# ProPrj_MID360V2_0_2025-05-30.net
KiCad netlist of a schematic drawn in EasyEDA Pro
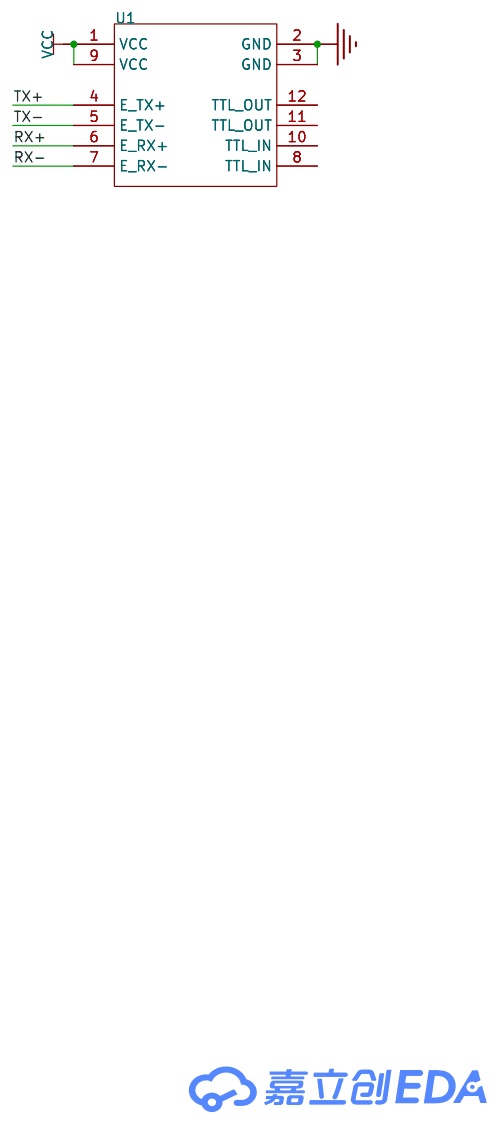
[diagram p0: schematic sheet]

(export (version "E")
  (design (tool "Eeschema 10.0.6"))
  (components
    (comp (ref "U1")
      (value "~")
      (footprint "easyedapro:M12_A_12")
      (libsource (lib "easyedapro") (part "mid360_m12"))
    )
  )
  (nets
    (net (code "1") (name "/RX+") (class "Default")
      (node (ref "U1") (pin "6") (pinfunction "E_RX+_6") (pintype "input"))
    )
    (net (code "2") (name "/RX-") (class "Default")
      (node (ref "U1") (pin "7") (pinfunction "E_RX-_7") (pintype "input"))
    )
    (net (code "3") (name "/TX+") (class "Default")
      (node (ref "U1") (pin "4") (pinfunction "E_TX+_4") (pintype "input"))
    )
    (net (code "4") (name "/TX-") (class "Default")
      (node (ref "U1") (pin "5") (pinfunction "E_TX-_5") (pintype "input"))
    )
    (net (code "5") (name "GND") (class "Default")
      (node (ref "U1") (pin "2") (pinfunction "GND_2") (pintype "input"))
      (node (ref "U1") (pin "3") (pinfunction "GND_3") (pintype "input"))
    )
    (net (code "6") (name "VCC") (class "Default")
      (node (ref "U1") (pin "1") (pinfunction "VCC_1") (pintype "input"))
      (node (ref "U1") (pin "9") (pinfunction "VCC_9") (pintype "input"))
    )
    (net (code "7") (name "unconnected-(U1-TTL_IN-Pad8)") (class "Default")
      (node (ref "U1") (pin "8") (pinfunction "TTL_IN_8") (pintype "input"))
    )
    (net (code "8") (name "unconnected-(U1-TTL_IN-Pad10)") (class "Default")
      (node (ref "U1") (pin "10") (pinfunction "TTL_IN_10") (pintype "input"))
    )
    (net (code "9") (name "unconnected-(U1-TTL_OUT-Pad11)") (class "Default")
      (node (ref "U1") (pin "11") (pinfunction "TTL_OUT_11") (pintype "input"))
    )
    (net (code "10") (name "unconnected-(U1-TTL_OUT-Pad12)") (class "Default")
      (node (ref "U1") (pin "12") (pinfunction "TTL_OUT_12") (pintype "input"))
    )
  )
)
